# 100.net
KiCad netlist of a schematic drawn in Altium Designer
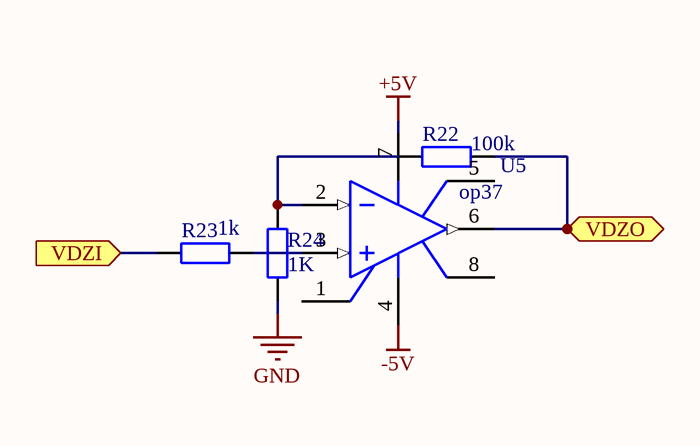
[diagram p0: 同向100倍放大.SchDoc]

(export (version "E")
  (design (tool "Eeschema 10.0.6"))
  (components
    (comp (ref "R22")
      (value "100k")
      (footprint "AXIAL-0.4")
      (description "Resistor")
      (fields (field (name "Comment") "Res2") (field (name "PUBLISHER") "Altium Limited"))
      (libsource (lib "") (part "Res2_1"))
    )
    (comp (ref "R23")
      (value "1k")
      (footprint "AXIAL-0.4")
      (description "Resistor")
      (fields (field (name "Comment") "Res2") (field (name "PUBLISHER") "Altium Limited"))
      (libsource (lib "") (part "Res2_1"))
    )
    (comp (ref "R24")
      (value "1K")
      (footprint "AXIAL-0.4")
      (description "Resistor")
      (fields (field (name "Comment") "Res2") (field (name "PUBLISHER") "Altium Limited"))
      (libsource (lib "Miscellaneous Devices") (part "Res2"))
    )
    (comp (ref "U5")
      (value "op37")
      (footprint "N-8_A")
      (description "Ultra-Low Offset Voltage Operational Amplifier")
      (fields (field (name "PUBLISHER") "Altium Limited"))
      (libsource (lib "AD Operational Amplifier") (part "ADOP07CN"))
    )
  )
  (nets
    (net (code "1") (name "+5V") (class "Default")
      (node (ref "U5") (pin "7") (pinfunction "V+_7") (pintype "power_in"))
    )
    (net (code "2") (name "-5V") (class "Default")
      (node (ref "U5") (pin "4") (pinfunction "V-_4") (pintype "power_in"))
    )
    (net (code "3") (name "/VDZI") (class "Default")
      (node (ref "R23") (pin "1") (pinfunction "1_1") (pintype "passive"))
    )
    (net (code "4") (name "/VDZO") (class "Default")
      (node (ref "R22") (pin "2") (pinfunction "2_2") (pintype "passive"))
      (node (ref "U5") (pin "6") (pinfunction "OUT_6") (pintype "output"))
    )
    (net (code "5") (name "GND") (class "Default")
      (node (ref "R24") (pin "1") (pinfunction "1_1") (pintype "passive"))
    )
    (net (code "6") (name "Net-(U5-IN+)") (class "Default")
      (node (ref "R23") (pin "2") (pinfunction "2_2") (pintype "passive"))
      (node (ref "U5") (pin "3") (pinfunction "IN+_3") (pintype "input"))
    )
    (net (code "7") (name "Net-(U5-IN-)") (class "Default")
      (node (ref "R22") (pin "1") (pinfunction "1_1") (pintype "passive"))
      (node (ref "R24") (pin "2") (pinfunction "2_2") (pintype "passive"))
      (node (ref "U5") (pin "2") (pinfunction "IN-_2") (pintype "input"))
    )
    (net (code "8") (name "unconnected-(U5-NC-Pad5)") (class "Default")
      (node (ref "U5") (pin "5") (pinfunction "NC_5") (pintype "passive"))
    )
    (net (code "9") (name "unconnected-(U5-NULL1-Pad1)") (class "Default")
      (node (ref "U5") (pin "1") (pinfunction "NULL1_1") (pintype "passive"))
    )
    (net (code "10") (name "unconnected-(U5-NULL2-Pad8)") (class "Default")
      (node (ref "U5") (pin "8") (pinfunction "NULL2_8") (pintype "passive"))
    )
  )
)
